# SSD1963-V1_0.net
KiCad netlist of a schematic drawn in EAGLE
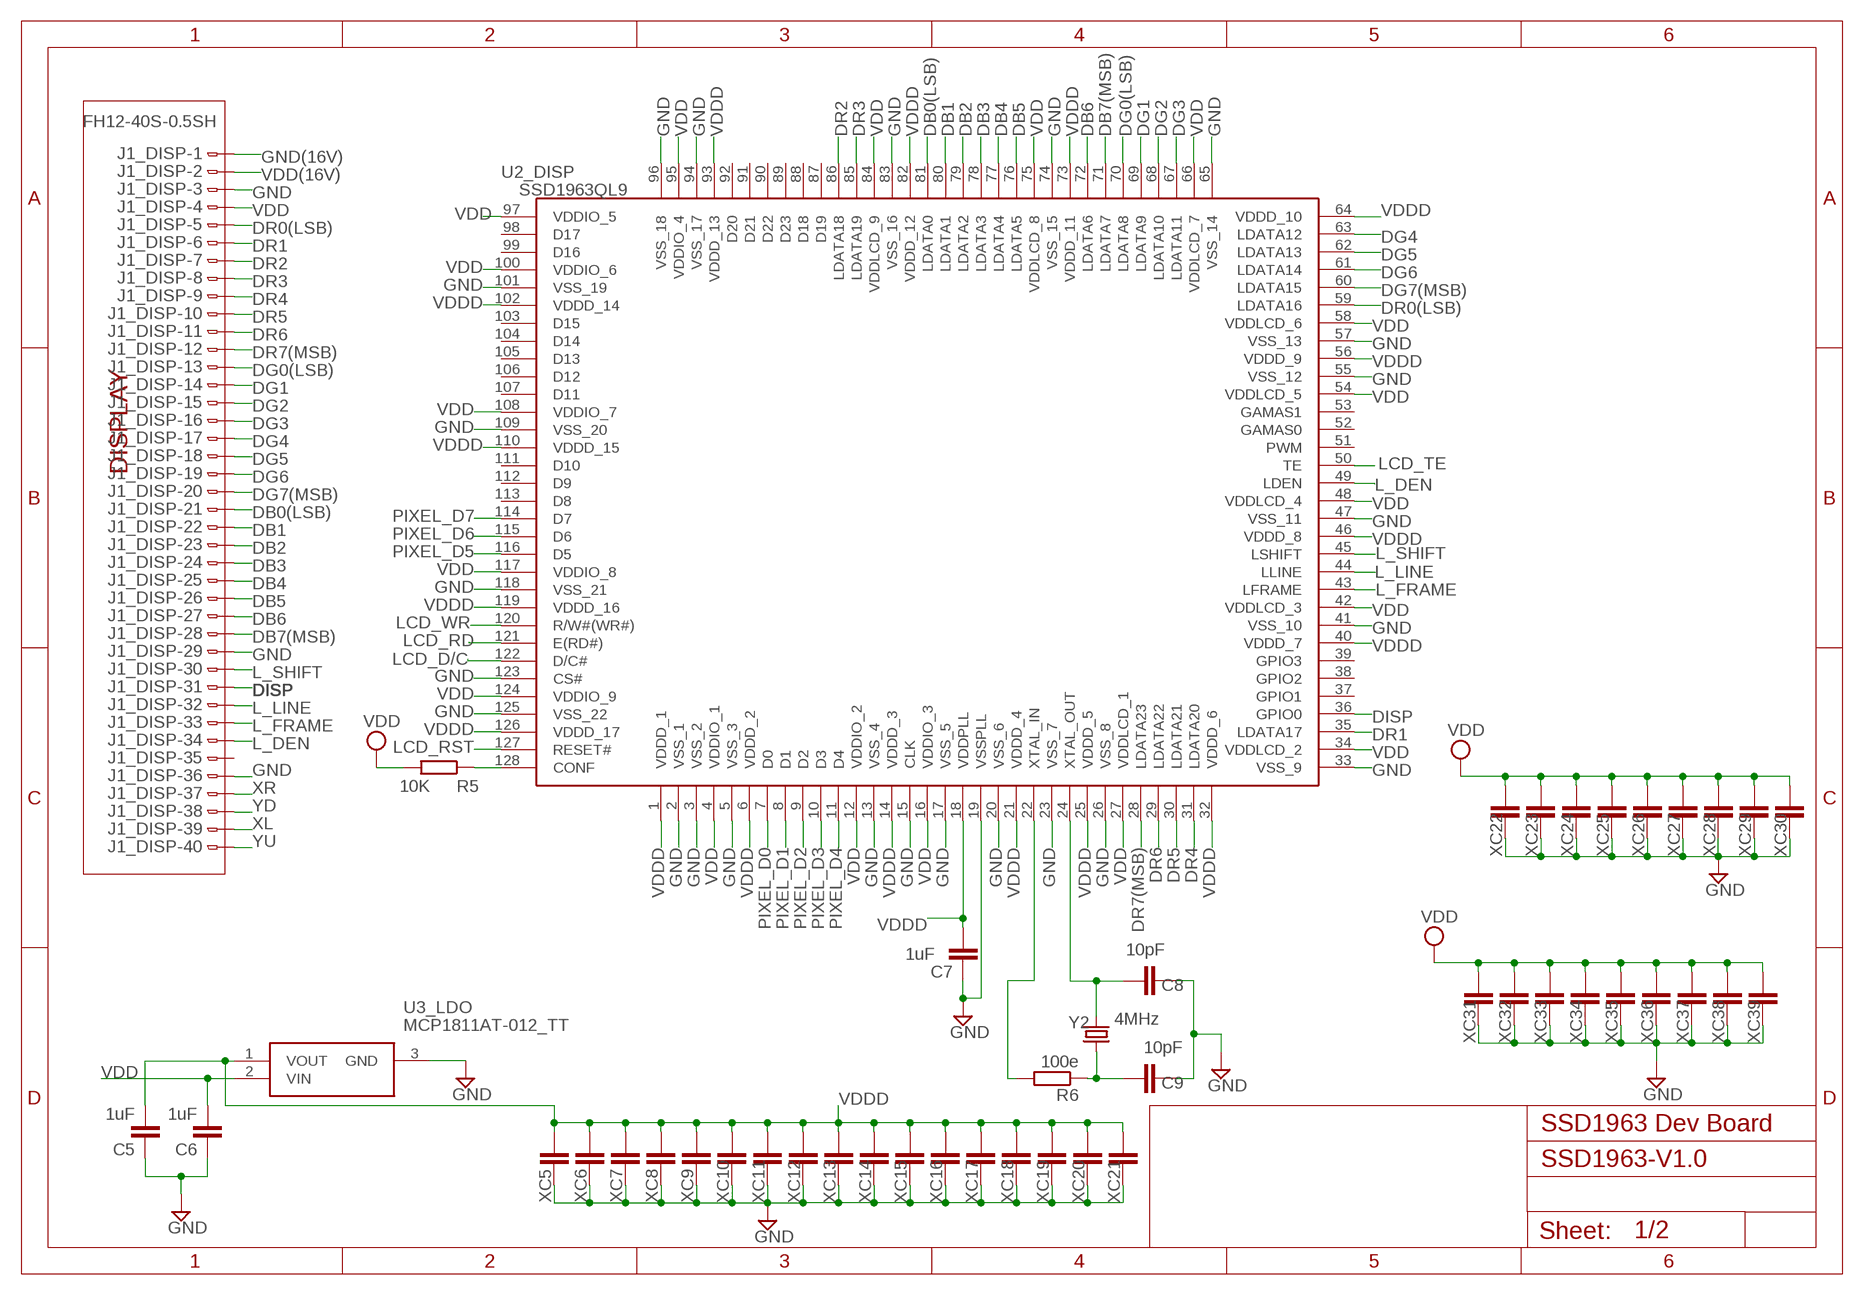
[diagram p0: schematic, sheet 1]
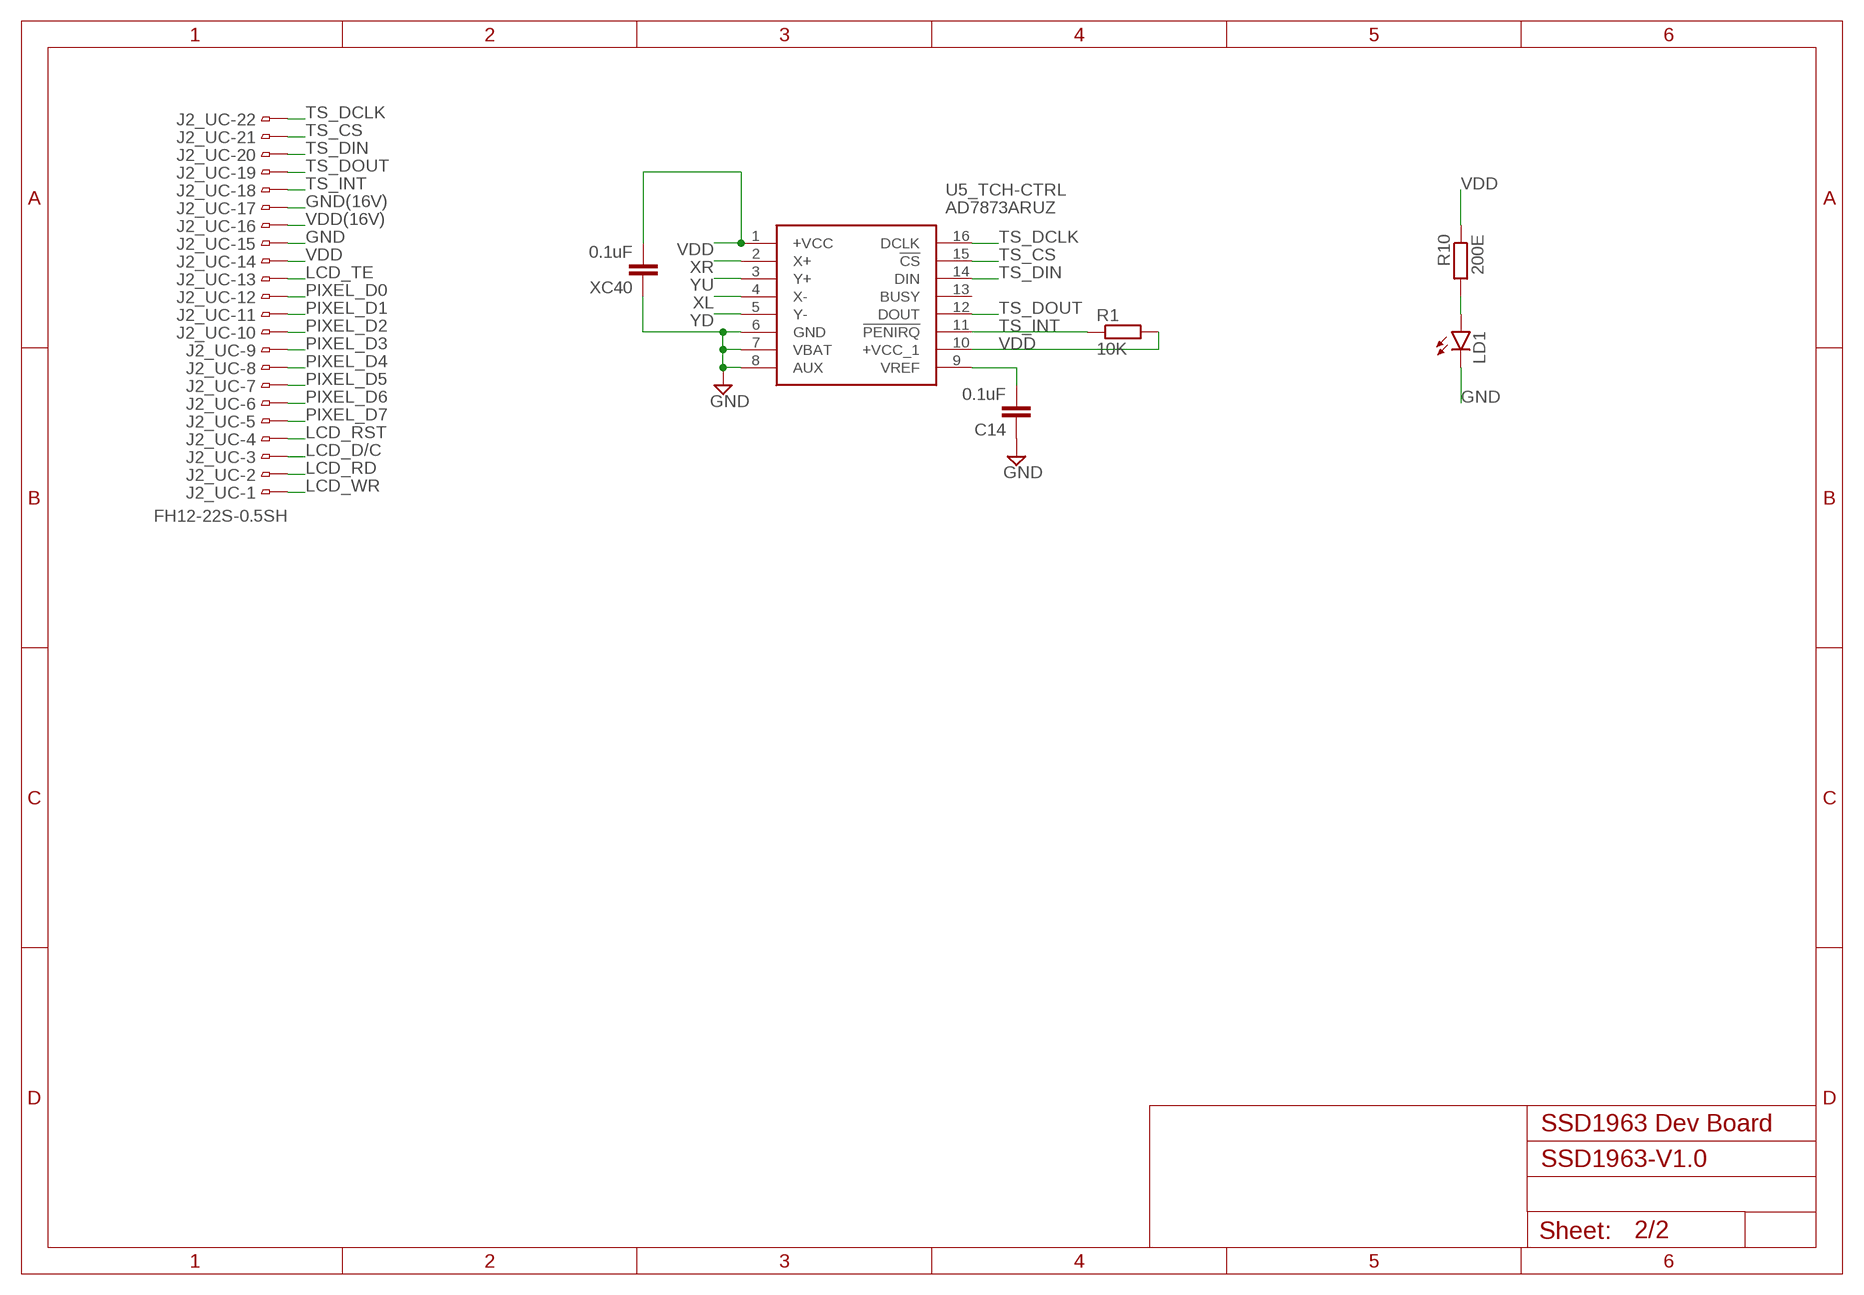
[diagram p1: schematic, sheet 2]

(export (version "E")
  (design (tool "Eeschema 10.0.6"))
  (components
    (comp (ref "C5")
      (value "1uF")
      (footprint "eagle-import:C1206")
      (description "Capacitor")
      (libsource (lib "eagle-import") (part "C-EUC1206"))
    )
    (comp (ref "C6")
      (value "1uF")
      (footprint "eagle-import:C1206")
      (description "Capacitor")
      (libsource (lib "eagle-import") (part "C-EUC1206"))
    )
    (comp (ref "C7")
      (value "1uF")
      (footprint "eagle-import:C0805")
      (description "Capacitor")
      (libsource (lib "eagle-import") (part "C-EUC0805"))
    )
    (comp (ref "C8")
      (value "10pF")
      (footprint "eagle-import:C1206")
      (description "Capacitor")
      (libsource (lib "eagle-import") (part "C-EUC1206"))
    )
    (comp (ref "C9")
      (value "10pF")
      (footprint "eagle-import:C1206")
      (description "Capacitor")
      (libsource (lib "eagle-import") (part "C-EUC1206"))
    )
    (comp (ref "J1_DISP")
      (value "FH12-40S-0.5SH")
      (footprint "eagle-import:FH12-40S-0.5SH")
      (description "0.5mm Pitch Connectors For FPC/FFC")
      (fields (field (name "MPN") "FH12-40S-0.5SH(55)"))
      (libsource (lib "eagle-import") (part "FH12-40S-0.5SH"))
    )
    (comp (ref "R5")
      (value "10K")
      (footprint "eagle-import:R1206")
      (description "Resistor")
      (libsource (lib "eagle-import") (part "R-EU_R1206"))
    )
    (comp (ref "R6")
      (value "100e")
      (footprint "eagle-import:R0805")
      (description "Resistor")
      (libsource (lib "eagle-import") (part "R-EU_R0805"))
    )
    (comp (ref "U2_DISP")
      (value "SSD1963QL9")
      (footprint "eagle-import:QFP40P1600X1600X160-128N")
      (libsource (lib "eagle-import") (part "SSD1963QL9"))
    )
    (comp (ref "U3_LDO")
      (value "MCP1811AT-012_TT")
      (footprint "eagle-import:SOT95P237X112-3N")
      (libsource (lib "eagle-import") (part "MCP1811AT-012_TT"))
    )
    (comp (ref "XC5")
      (value "0.1uF")
      (footprint "eagle-import:C0805")
      (description "Capacitor")
      (libsource (lib "eagle-import") (part "C-EUC0805"))
    )
    (comp (ref "XC6")
      (value "0.1uF")
      (footprint "eagle-import:C0805")
      (description "Capacitor")
      (libsource (lib "eagle-import") (part "C-EUC0805"))
    )
    (comp (ref "XC7")
      (value "0.1uF")
      (footprint "eagle-import:C0805")
      (description "Capacitor")
      (libsource (lib "eagle-import") (part "C-EUC0805"))
    )
    (comp (ref "XC8")
      (value "0.1uF")
      (footprint "eagle-import:C0805")
      (description "Capacitor")
      (libsource (lib "eagle-import") (part "C-EUC0805"))
    )
    (comp (ref "XC9")
      (value "0.1uF")
      (footprint "eagle-import:C0805")
      (description "Capacitor")
      (libsource (lib "eagle-import") (part "C-EUC0805"))
    )
    (comp (ref "XC10")
      (value "0.1uF")
      (footprint "eagle-import:C0805")
      (description "Capacitor")
      (libsource (lib "eagle-import") (part "C-EUC0805"))
    )
    (comp (ref "XC11")
      (value "0.1uF")
      (footprint "eagle-import:C0805")
      (description "Capacitor")
      (libsource (lib "eagle-import") (part "C-EUC0805"))
    )
    (comp (ref "XC12")
      (value "0.1uF")
      (footprint "eagle-import:C0805")
      (description "Capacitor")
      (libsource (lib "eagle-import") (part "C-EUC0805"))
    )
    (comp (ref "XC13")
      (value "0.1uF")
      (footprint "eagle-import:C0805")
      (description "Capacitor")
      (libsource (lib "eagle-import") (part "C-EUC0805"))
    )
    (comp (ref "XC14")
      (value "0.1uF")
      (footprint "eagle-import:C0805")
      (description "Capacitor")
      (libsource (lib "eagle-import") (part "C-EUC0805"))
    )
    (comp (ref "XC15")
      (value "0.1uF")
      (footprint "eagle-import:C0805")
      (description "Capacitor")
      (libsource (lib "eagle-import") (part "C-EUC0805"))
    )
    (comp (ref "XC16")
      (value "0.1uF")
      (footprint "eagle-import:C0805")
      (description "Capacitor")
      (libsource (lib "eagle-import") (part "C-EUC0805"))
    )
    (comp (ref "XC17")
      (value "0.1uF")
      (footprint "eagle-import:C0805")
      (description "Capacitor")
      (libsource (lib "eagle-import") (part "C-EUC0805"))
    )
    (comp (ref "XC18")
      (value "0.1uF")
      (footprint "eagle-import:C0805")
      (description "Capacitor")
      (libsource (lib "eagle-import") (part "C-EUC0805"))
    )
    (comp (ref "XC19")
      (value "0.1uF")
      (footprint "eagle-import:C0805")
      (description "Capacitor")
      (libsource (lib "eagle-import") (part "C-EUC0805"))
    )
    (comp (ref "XC20")
      (value "0.1uF")
      (footprint "eagle-import:C0805")
      (description "Capacitor")
      (libsource (lib "eagle-import") (part "C-EUC0805"))
    )
    (comp (ref "XC21")
      (value "0.1uF")
      (footprint "eagle-import:C0805")
      (description "Capacitor")
      (libsource (lib "eagle-import") (part "C-EUC0805"))
    )
    (comp (ref "XC22")
      (value "0.1uF")
      (footprint "eagle-import:C0805")
      (description "Capacitor")
      (libsource (lib "eagle-import") (part "C-EUC0805"))
    )
    (comp (ref "XC23")
      (value "0.1uF")
      (footprint "eagle-import:C0805")
      (description "Capacitor")
      (libsource (lib "eagle-import") (part "C-EUC0805"))
    )
    (comp (ref "XC24")
      (value "0.1uF")
      (footprint "eagle-import:C0805")
      (description "Capacitor")
      (libsource (lib "eagle-import") (part "C-EUC0805"))
    )
    (comp (ref "XC25")
      (value "0.1uF")
      (footprint "eagle-import:C0805")
      (description "Capacitor")
      (libsource (lib "eagle-import") (part "C-EUC0805"))
    )
    (comp (ref "XC26")
      (value "0.1uF")
      (footprint "eagle-import:C0805")
      (description "Capacitor")
      (libsource (lib "eagle-import") (part "C-EUC0805"))
    )
    (comp (ref "XC27")
      (value "0.1uF")
      (footprint "eagle-import:C0805")
      (description "Capacitor")
      (libsource (lib "eagle-import") (part "C-EUC0805"))
    )
    (comp (ref "XC28")
      (value "0.1uF")
      (footprint "eagle-import:C0805")
      (description "Capacitor")
      (libsource (lib "eagle-import") (part "C-EUC0805"))
    )
    (comp (ref "XC29")
      (value "0.1uF")
      (footprint "eagle-import:C0805")
      (description "Capacitor")
      (libsource (lib "eagle-import") (part "C-EUC0805"))
    )
    (comp (ref "XC30")
      (value "0.1uF")
      (footprint "eagle-import:C0805")
      (description "Capacitor")
      (libsource (lib "eagle-import") (part "C-EUC0805"))
    )
    (comp (ref "XC31")
      (value "0.1uF")
      (footprint "eagle-import:C0805")
      (description "Capacitor")
      (libsource (lib "eagle-import") (part "C-EUC0805"))
    )
    (comp (ref "XC32")
      (value "0.1uF")
      (footprint "eagle-import:C0805")
      (description "Capacitor")
      (libsource (lib "eagle-import") (part "C-EUC0805"))
    )
    (comp (ref "XC33")
      (value "0.1uF")
      (footprint "eagle-import:C0805")
      (description "Capacitor")
      (libsource (lib "eagle-import") (part "C-EUC0805"))
    )
    (comp (ref "XC34")
      (value "0.1uF")
      (footprint "eagle-import:C0805")
      (description "Capacitor")
      (libsource (lib "eagle-import") (part "C-EUC0805"))
    )
    (comp (ref "XC35")
      (value "0.1uF")
      (footprint "eagle-import:C0805")
      (description "Capacitor")
      (libsource (lib "eagle-import") (part "C-EUC0805"))
    )
    (comp (ref "XC36")
      (value "0.1uF")
      (footprint "eagle-import:C0805")
      (description "Capacitor")
      (libsource (lib "eagle-import") (part "C-EUC0805"))
    )
    (comp (ref "XC37")
      (value "0.1uF")
      (footprint "eagle-import:C0805")
      (description "Capacitor")
      (libsource (lib "eagle-import") (part "C-EUC0805"))
    )
    (comp (ref "XC38")
      (value "0.1uF")
      (footprint "eagle-import:C0805")
      (description "Capacitor")
      (libsource (lib "eagle-import") (part "C-EUC0805"))
    )
    (comp (ref "XC39")
      (value "0.1uF")
      (footprint "eagle-import:C0805")
      (description "Capacitor")
      (libsource (lib "eagle-import") (part "C-EUC0805"))
    )
    (comp (ref "Y2")
      (value "4MHz")
      (footprint "eagle-import:HC49UP")
      (description "Crystal 4MHz")
      (libsource (lib "eagle-import") (part "CRYSTALHC49UP"))
    )
    (comp (ref "C14")
      (value "0.1uF")
      (footprint "eagle-import:C1206")
      (description "Capacitor")
      (libsource (lib "eagle-import") (part "C-EUC1206"))
    )
    (comp (ref "J2_UC")
      (value "FH12-22S-0.5SH")
      (footprint "eagle-import:FH12-22S-0.5SH")
      (libsource (lib "eagle-import") (part "FH12-22S-0.5SH"))
    )
    (comp (ref "LD1")
      (value "LEDCHIPLED_1206")
      (footprint "eagle-import:CHIPLED_1206")
      (description "SMD Green LED")
      (libsource (lib "eagle-import") (part "LEDCHIPLED_1206"))
    )
    (comp (ref "R1")
      (value "10K")
      (footprint "eagle-import:R1206")
      (libsource (lib "eagle-import") (part "R-EU_R1206"))
    )
    (comp (ref "R10")
      (value "200E")
      (footprint "eagle-import:R1206")
      (description "Resistor")
      (libsource (lib "eagle-import") (part "R-EU_R1206"))
    )
    (comp (ref "U5_TCH-CTRL")
      (value "AD7873ARUZ")
      (footprint "eagle-import:SOP64P600X175-16N")
      (libsource (lib "eagle-import") (part "AD7873ARUZ"))
    )
    (comp (ref "XC40")
      (value "0.1uF")
      (footprint "eagle-import:C0805")
      (description "Capacitor")
      (libsource (lib "eagle-import") (part "C-EUC0805"))
    )
  )
  (nets
    (net (code "1") (name "DB0(LSB)") (class "Default")
      (node (ref "J1_DISP") (pin "20") (pinfunction "1_20") (pintype "passive"))
      (node (ref "U2_DISP") (pin "81") (pinfunction "LDATA0_81") (pintype "bidirectional"))
    )
    (net (code "2") (name "DB1") (class "Default")
      (node (ref "J1_DISP") (pin "19") (pinfunction "1_19") (pintype "passive"))
      (node (ref "U2_DISP") (pin "80") (pinfunction "LDATA1_80") (pintype "bidirectional"))
    )
    (net (code "3") (name "DB2") (class "Default")
      (node (ref "J1_DISP") (pin "18") (pinfunction "1_18") (pintype "passive"))
      (node (ref "U2_DISP") (pin "79") (pinfunction "LDATA2_79") (pintype "bidirectional"))
    )
    (net (code "4") (name "DB3") (class "Default")
      (node (ref "J1_DISP") (pin "17") (pinfunction "1_17") (pintype "passive"))
      (node (ref "U2_DISP") (pin "78") (pinfunction "LDATA3_78") (pintype "bidirectional"))
    )
    (net (code "5") (name "DB4") (class "Default")
      (node (ref "J1_DISP") (pin "16") (pinfunction "1_16") (pintype "passive"))
      (node (ref "U2_DISP") (pin "77") (pinfunction "LDATA4_77") (pintype "bidirectional"))
    )
    (net (code "6") (name "DB5") (class "Default")
      (node (ref "J1_DISP") (pin "15") (pinfunction "1_15") (pintype "passive"))
      (node (ref "U2_DISP") (pin "76") (pinfunction "LDATA5_76") (pintype "bidirectional"))
    )
    (net (code "7") (name "DB6") (class "Default")
      (node (ref "J1_DISP") (pin "14") (pinfunction "1_14") (pintype "passive"))
      (node (ref "U2_DISP") (pin "72") (pinfunction "LDATA6_72") (pintype "bidirectional"))
    )
    (net (code "8") (name "DB7(MSB)") (class "Default")
      (node (ref "J1_DISP") (pin "13") (pinfunction "1_13") (pintype "passive"))
      (node (ref "U2_DISP") (pin "71") (pinfunction "LDATA7_71") (pintype "bidirectional"))
    )
    (net (code "9") (name "DG0(LSB)") (class "Default")
      (node (ref "J1_DISP") (pin "28") (pinfunction "1_28") (pintype "passive"))
      (node (ref "U2_DISP") (pin "70") (pinfunction "LDATA8_70") (pintype "bidirectional"))
    )
    (net (code "10") (name "DG1") (class "Default")
      (node (ref "J1_DISP") (pin "27") (pinfunction "1_27") (pintype "passive"))
      (node (ref "U2_DISP") (pin "69") (pinfunction "LDATA9_69") (pintype "bidirectional"))
    )
    (net (code "11") (name "DG2") (class "Default")
      (node (ref "J1_DISP") (pin "26") (pinfunction "1_26") (pintype "passive"))
      (node (ref "U2_DISP") (pin "68") (pinfunction "LDATA10_68") (pintype "bidirectional"))
    )
    (net (code "12") (name "DG3") (class "Default")
      (node (ref "J1_DISP") (pin "25") (pinfunction "1_25") (pintype "passive"))
      (node (ref "U2_DISP") (pin "67") (pinfunction "LDATA11_67") (pintype "bidirectional"))
    )
    (net (code "13") (name "DG4") (class "Default")
      (node (ref "J1_DISP") (pin "24") (pinfunction "1_24") (pintype "passive"))
      (node (ref "U2_DISP") (pin "63") (pinfunction "LDATA12_63") (pintype "bidirectional"))
    )
    (net (code "14") (name "DG5") (class "Default")
      (node (ref "J1_DISP") (pin "23") (pinfunction "1_23") (pintype "passive"))
      (node (ref "U2_DISP") (pin "62") (pinfunction "LDATA13_62") (pintype "bidirectional"))
    )
    (net (code "15") (name "DG6") (class "Default")
      (node (ref "J1_DISP") (pin "22") (pinfunction "1_22") (pintype "passive"))
      (node (ref "U2_DISP") (pin "61") (pinfunction "LDATA14_61") (pintype "bidirectional"))
    )
    (net (code "16") (name "DG7(MSB)") (class "Default")
      (node (ref "J1_DISP") (pin "21") (pinfunction "1_21") (pintype "passive"))
      (node (ref "U2_DISP") (pin "60") (pinfunction "LDATA15_60") (pintype "bidirectional"))
    )
    (net (code "17") (name "DISP") (class "Default")
      (node (ref "J1_DISP") (pin "10") (pinfunction "1_10") (pintype "passive"))
      (node (ref "U2_DISP") (pin "36") (pinfunction "GPIO0_36") (pintype "bidirectional"))
    )
    (net (code "18") (name "DR0(LSB)") (class "Default")
      (node (ref "J1_DISP") (pin "36") (pinfunction "1_36") (pintype "passive"))
      (node (ref "U2_DISP") (pin "59") (pinfunction "LDATA16_59") (pintype "bidirectional"))
    )
    (net (code "19") (name "DR1") (class "Default")
      (node (ref "J1_DISP") (pin "35") (pinfunction "1_35") (pintype "passive"))
      (node (ref "U2_DISP") (pin "35") (pinfunction "LDATA17_35") (pintype "bidirectional"))
    )
    (net (code "20") (name "DR2") (class "Default")
      (node (ref "J1_DISP") (pin "34") (pinfunction "1_34") (pintype "passive"))
      (node (ref "U2_DISP") (pin "86") (pinfunction "LDATA18_86") (pintype "bidirectional"))
    )
    (net (code "21") (name "DR3") (class "Default")
      (node (ref "J1_DISP") (pin "33") (pinfunction "1_33") (pintype "passive"))
      (node (ref "U2_DISP") (pin "85") (pinfunction "LDATA19_85") (pintype "bidirectional"))
    )
    (net (code "22") (name "DR4") (class "Default")
      (node (ref "J1_DISP") (pin "32") (pinfunction "1_32") (pintype "passive"))
      (node (ref "U2_DISP") (pin "31") (pinfunction "LDATA20_31") (pintype "bidirectional"))
    )
    (net (code "23") (name "DR5") (class "Default")
      (node (ref "J1_DISP") (pin "31") (pinfunction "1_31") (pintype "passive"))
      (node (ref "U2_DISP") (pin "30") (pinfunction "LDATA21_30") (pintype "bidirectional"))
    )
    (net (code "24") (name "DR6") (class "Default")
      (node (ref "J1_DISP") (pin "30") (pinfunction "1_30") (pintype "passive"))
      (node (ref "U2_DISP") (pin "29") (pinfunction "LDATA22_29") (pintype "bidirectional"))
    )
    (net (code "25") (name "DR7(MSB)") (class "Default")
      (node (ref "J1_DISP") (pin "29") (pinfunction "1_29") (pintype "passive"))
      (node (ref "U2_DISP") (pin "28") (pinfunction "LDATA23_28") (pintype "bidirectional"))
    )
    (net (code "26") (name "GND") (class "Default")
      (node (ref "C14") (pin "1") (pinfunction "1_1") (pintype "passive"))
      (node (ref "C5") (pin "1") (pinfunction "1_1") (pintype "passive"))
      (node (ref "C6") (pin "1") (pinfunction "1_1") (pintype "passive"))
      (node (ref "C7") (pin "1") (pinfunction "1_1") (pintype "passive"))
      (node (ref "C8") (pin "1") (pinfunction "1_1") (pintype "passive"))
      (node (ref "C9") (pin "1") (pinfunction "1_1") (pintype "passive"))
      (node (ref "J1_DISP") (pin "12") (pinfunction "1_12") (pintype "passive"))
      (node (ref "J1_DISP") (pin "38") (pinfunction "1_38") (pintype "passive"))
      (node (ref "J1_DISP") (pin "5") (pinfunction "1_5") (pintype "passive"))
      (node (ref "J2_UC") (pin "15") (pinfunction "1_15") (pintype "passive"))
      (node (ref "LD1") (pin "C") (pinfunction "C_C") (pintype "passive"))
      (node (ref "U2_DISP") (pin "101") (pinfunction "VSS_19_101") (pintype "bidirectional"))
      (node (ref "U2_DISP") (pin "109") (pinfunction "VSS_20_109") (pintype "bidirectional"))
      (node (ref "U2_DISP") (pin "118") (pinfunction "VSS_21_118") (pintype "bidirectional"))
      (node (ref "U2_DISP") (pin "123") (pinfunction "CS#_123") (pintype "bidirectional"))
      (node (ref "U2_DISP") (pin "125") (pinfunction "VSS_22_125") (pintype "bidirectional"))
      (node (ref "U2_DISP") (pin "13") (pinfunction "VSS_4_13") (pintype "bidirectional"))
      (node (ref "U2_DISP") (pin "15") (pinfunction "CLK_15") (pintype "bidirectional"))
      (node (ref "U2_DISP") (pin "17") (pinfunction "VSS_5_17") (pintype "bidirectional"))
      (node (ref "U2_DISP") (pin "19") (pinfunction "VSSPLL_19") (pintype "bidirectional"))
      (node (ref "U2_DISP") (pin "2") (pinfunction "VSS_1_2") (pintype "bidirectional"))
      (node (ref "U2_DISP") (pin "20") (pinfunction "VSS_6_20") (pintype "bidirectional"))
      (node (ref "U2_DISP") (pin "23") (pinfunction "VSS_7_23") (pintype "bidirectional"))
      (node (ref "U2_DISP") (pin "26") (pinfunction "VSS_8_26") (pintype "bidirectional"))
      (node (ref "U2_DISP") (pin "3") (pinfunction "VSS_2_3") (pintype "bidirectional"))
      (node (ref "U2_DISP") (pin "33") (pinfunction "VSS_9_33") (pintype "bidirectional"))
      (node (ref "U2_DISP") (pin "41") (pinfunction "VSS_10_41") (pintype "bidirectional"))
      (node (ref "U2_DISP") (pin "47") (pinfunction "VSS_11_47") (pintype "bidirectional"))
      (node (ref "U2_DISP") (pin "5") (pinfunction "VSS_3_5") (pintype "bidirectional"))
      (node (ref "U2_DISP") (pin "55") (pinfunction "VSS_12_55") (pintype "bidirectional"))
      (node (ref "U2_DISP") (pin "57") (pinfunction "VSS_13_57") (pintype "bidirectional"))
      (node (ref "U2_DISP") (pin "65") (pinfunction "VSS_14_65") (pintype "bidirectional"))
      (node (ref "U2_DISP") (pin "74") (pinfunction "VSS_15_74") (pintype "bidirectional"))
      (node (ref "U2_DISP") (pin "83") (pinfunction "VSS_16_83") (pintype "bidirectional"))
      (node (ref "U2_DISP") (pin "94") (pinfunction "VSS_17_94") (pintype "bidirectional"))
      (node (ref "U2_DISP") (pin "96") (pinfunction "VSS_18_96") (pintype "bidirectional"))
      (node (ref "U3_LDO") (pin "3") (pinfunction "GND_3") (pintype "bidirectional"))
      (node (ref "U5_TCH-CTRL") (pin "6") (pinfunction "GND_6") (pintype "power_in"))
      (node (ref "U5_TCH-CTRL") (pin "7") (pinfunction "VBAT_7") (pintype "bidirectional"))
      (node (ref "U5_TCH-CTRL") (pin "8") (pinfunction "AUX_8") (pintype "bidirectional"))
      (node (ref "XC10") (pin "1") (pinfunction "1_1") (pintype "passive"))
      (node (ref "XC11") (pin "1") (pinfunction "1_1") (pintype "passive"))
      (node (ref "XC12") (pin "1") (pinfunction "1_1") (pintype "passive"))
      (node (ref "XC13") (pin "1") (pinfunction "1_1") (pintype "passive"))
      (node (ref "XC14") (pin "1") (pinfunction "1_1") (pintype "passive"))
      (node (ref "XC15") (pin "1") (pinfunction "1_1") (pintype "passive"))
      (node (ref "XC16") (pin "1") (pinfunction "1_1") (pintype "passive"))
      (node (ref "XC17") (pin "1") (pinfunction "1_1") (pintype "passive"))
      (node (ref "XC18") (pin "1") (pinfunction "1_1") (pintype "passive"))
      (node (ref "XC19") (pin "1") (pinfunction "1_1") (pintype "passive"))
      (node (ref "XC20") (pin "1") (pinfunction "1_1") (pintype "passive"))
      (node (ref "XC21") (pin "1") (pinfunction "1_1") (pintype "passive"))
      (node (ref "XC22") (pin "1") (pinfunction "1_1") (pintype "passive"))
      (node (ref "XC23") (pin "1") (pinfunction "1_1") (pintype "passive"))
      (node (ref "XC24") (pin "1") (pinfunction "1_1") (pintype "passive"))
      (node (ref "XC25") (pin "1") (pinfunction "1_1") (pintype "passive"))
      (node (ref "XC26") (pin "1") (pinfunction "1_1") (pintype "passive"))
      (node (ref "XC27") (pin "1") (pinfunction "1_1") (pintype "passive"))
      (node (ref "XC28") (pin "1") (pinfunction "1_1") (pintype "passive"))
      (node (ref "XC29") (pin "1") (pinfunction "1_1") (pintype "passive"))
      (node (ref "XC30") (pin "1") (pinfunction "1_1") (pintype "passive"))
      (node (ref "XC31") (pin "1") (pinfunction "1_1") (pintype "passive"))
      (node (ref "XC32") (pin "1") (pinfunction "1_1") (pintype "passive"))
      (node (ref "XC33") (pin "1") (pinfunction "1_1") (pintype "passive"))
      (node (ref "XC34") (pin "1") (pinfunction "1_1") (pintype "passive"))
      (node (ref "XC35") (pin "1") (pinfunction "1_1") (pintype "passive"))
      (node (ref "XC36") (pin "1") (pinfunction "1_1") (pintype "passive"))
      (node (ref "XC37") (pin "1") (pinfunction "1_1") (pintype "passive"))
      (node (ref "XC38") (pin "1") (pinfunction "1_1") (pintype "passive"))
      (node (ref "XC39") (pin "1") (pinfunction "1_1") (pintype "passive"))
      (node (ref "XC40") (pin "1") (pinfunction "1_1") (pintype "passive"))
      (node (ref "XC5") (pin "1") (pinfunction "1_1") (pintype "passive"))
      (node (ref "XC6") (pin "1") (pinfunction "1_1") (pintype "passive"))
      (node (ref "XC7") (pin "1") (pinfunction "1_1") (pintype "passive"))
      (node (ref "XC8") (pin "1") (pinfunction "1_1") (pintype "passive"))
      (node (ref "XC9") (pin "1") (pinfunction "1_1") (pintype "passive"))
    )
    (net (code "27") (name "GND(16V)") (class "Default")
      (node (ref "J1_DISP") (pin "40") (pinfunction "1_40") (pintype "passive"))
      (node (ref "J2_UC") (pin "17") (pinfunction "1_17") (pintype "passive"))
    )
    (net (code "28") (name "LCD_D{slash}C") (class "Default")
      (node (ref "J2_UC") (pin "3") (pinfunction "1_3") (pintype "passive"))
      (node (ref "U2_DISP") (pin "122") (pinfunction "D/C#_122") (pintype "bidirectional"))
    )
    (net (code "29") (name "LCD_RD") (class "Default")
      (node (ref "J2_UC") (pin "2") (pinfunction "1_2") (pintype "passive"))
      (node (ref "U2_DISP") (pin "121") (pinfunction "E(RD#)_121") (pintype "bidirectional"))
    )
    (net (code "30") (name "LCD_RST") (class "Default")
      (node (ref "J2_UC") (pin "4") (pinfunction "1_4") (pintype "passive"))
      (node (ref "U2_DISP") (pin "127") (pinfunction "RESET#_127") (pintype "bidirectional"))
    )
    (net (code "31") (name "LCD_TE") (class "Default")
      (node (ref "J2_UC") (pin "13") (pinfunction "1_13") (pintype "passive"))
      (node (ref "U2_DISP") (pin "50") (pinfunction "TE_50") (pintype "bidirectional"))
    )
    (net (code "32") (name "LCD_WR") (class "Default")
      (node (ref "J2_UC") (pin "1") (pinfunction "1_1") (pintype "passive"))
      (node (ref "U2_DISP") (pin "120") (pinfunction "R/W#(WR#)_120") (pintype "bidirectional"))
    )
    (net (code "33") (name "L_DEN") (class "Default")
      (node (ref "J1_DISP") (pin "7") (pinfunction "1_7") (pintype "passive"))
      (node (ref "U2_DISP") (pin "49") (pinfunction "LDEN_49") (pintype "bidirectional"))
    )
    (net (code "34") (name "L_FRAME") (class "Default")
      (node (ref "J1_DISP") (pin "8") (pinfunction "1_8") (pintype "passive"))
      (node (ref "U2_DISP") (pin "43") (pinfunction "LFRAME_43") (pintype "bidirectional"))
    )
    (net (code "35") (name "L_LINE") (class "Default")
      (node (ref "J1_DISP") (pin "9") (pinfunction "1_9") (pintype "passive"))
      (node (ref "U2_DISP") (pin "44") (pinfunction "LLINE_44") (pintype "bidirectional"))
    )
    (net (code "36") (name "L_SHIFT") (class "Default")
      (node (ref "J1_DISP") (pin "11") (pinfunction "1_11") (pintype "passive"))
      (node (ref "U2_DISP") (pin "45") (pinfunction "LSHIFT_45") (pintype "bidirectional"))
    )
    (net (code "37") (name "Net-(C9-Pad2)") (class "Default")
      (node (ref "C9") (pin "2") (pinfunction "2_2") (pintype "passive"))
      (node (ref "R6") (pin "1") (pinfunction "1_1") (pintype "passive"))
      (node (ref "Y2") (pin "1") (pinfunction "1_1") (pintype "passive"))
    )
    (net (code "38") (name "Net-(LD1-PadA)") (class "Default")
      (node (ref "LD1") (pin "A") (pinfunction "A_A") (pintype "passive"))
      (node (ref "R10") (pin "2") (pinfunction "2_2") (pintype "passive"))
    )
    (net (code "39") (name "Net-(U2_DISP-CONF)") (class "Default")
      (node (ref "R5") (pin "1") (pinfunction "1_1") (pintype "passive"))
      (node (ref "U2_DISP") (pin "128") (pinfunction "CONF_128") (pintype "bidirectional"))
    )
    (net (code "40") (name "Net-(U2_DISP-XTAL_IN)") (class "Default")
      (node (ref "R6") (pin "2") (pinfunction "2_2") (pintype "passive"))
      (node (ref "U2_DISP") (pin "22") (pinfunction "XTAL_IN_22") (pintype "bidirectional"))
    )
    (net (code "41") (name "Net-(U2_DISP-XTAL_OUT)") (class "Default")
      (node (ref "C8") (pin "2") (pinfunction "2_2") (pintype "passive"))
      (node (ref "U2_DISP") (pin "24") (pinfunction "XTAL_OUT_24") (pintype "bidirectional"))
      (node (ref "Y2") (pin "2") (pinfunction "2_2") (pintype "passive"))
    )
    (net (code "42") (name "Net-(U5_TCH-CTRL-VREF)") (class "Default")
      (node (ref "C14") (pin "2") (pinfunction "2_2") (pintype "passive"))
      (node (ref "U5_TCH-CTRL") (pin "9") (pinfunction "VREF_9") (pintype "input"))
    )
    (net (code "43") (name "PIXEL_D0") (class "Default")
      (node (ref "J2_UC") (pin "12") (pinfunction "1_12") (pintype "passive"))
      (node (ref "U2_DISP") (pin "7") (pinfunction "D0_7") (pintype "bidirectional"))
    )
    (net (code "44") (name "PIXEL_D1") (class "Default")
      (node (ref "J2_UC") (pin "11") (pinfunction "1_11") (pintype "passive"))
      (node (ref "U2_DISP") (pin "8") (pinfunction "D1_8") (pintype "bidirectional"))
    )
    (net (code "45") (name "PIXEL_D2") (class "Default")
      (node (ref "J2_UC") (pin "10") (pinfunction "1_10") (pintype "passive"))
      (node (ref "U2_DISP") (pin "9") (pinfunction "D2_9") (pintype "bidirectional"))
    )
    (net (code "46") (name "PIXEL_D3") (class "Default")
      (node (ref "J2_UC") (pin "9") (pinfunction "1_9") (pintype "passive"))
      (node (ref "U2_DISP") (pin "10") (pinfunction "D3_10") (pintype "bidirectional"))
    )
    (net (code "47") (name "PIXEL_D4") (class "Default")
      (node (ref "J2_UC") (pin "8") (pinfunction "1_8") (pintype "passive"))
      (node (ref "U2_DISP") (pin "11") (pinfunction "D4_11") (pintype "bidirectional"))
    )
    (net (code "48") (name "PIXEL_D5") (class "Default")
      (node (ref "J2_UC") (pin "7") (pinfunction "1_7") (pintype "passive"))
      (node (ref "U2_DISP") (pin "116") (pinfunction "D5_116") (pintype "bidirectional"))
    )
    (net (code "49") (name "PIXEL_D6") (class "Default")
      (node (ref "J2_UC") (pin "6") (pinfunction "1_6") (pintype "passive"))
      (node (ref "U2_DISP") (pin "115") (pinfunction "D6_115") (pintype "bidirectional"))
    )
    (net (code "50") (name "PIXEL_D7") (class "Default")
      (node (ref "J2_UC") (pin "5") (pinfunction "1_5") (pintype "passive"))
      (node (ref "U2_DISP") (pin "114") (pinfunction "D7_114") (pintype "bidirectional"))
    )
    (net (code "51") (name "TS_CS") (class "Default")
      (node (ref "J2_UC") (pin "21") (pinfunction "1_21") (pintype "passive"))
      (node (ref "U5_TCH-CTRL") (pin "15") (pinfunction "~{CS}_15") (pintype "input"))
    )
    (net (code "52") (name "TS_DCLK") (class "Default")
      (node (ref "J2_UC") (pin "22") (pinfunction "1_22") (pintype "passive"))
      (node (ref "U5_TCH-CTRL") (pin "16") (pinfunction "DCLK_16") (pintype "input"))
    )
    (net (code "53") (name "TS_DIN") (class "Default")
      (node (ref "J2_UC") (pin "20") (pinfunction "1_20") (pintype "passive"))
      (node (ref "U5_TCH-CTRL") (pin "14") (pinfunction "DIN_14") (pintype "input"))
    )
    (net (code "54") (name "TS_DOUT") (class "Default")
      (node (ref "J2_UC") (pin "19") (pinfunction "1_19") (pintype "passive"))
      (node (ref "U5_TCH-CTRL") (pin "12") (pinfunction "DOUT_12") (pintype "output"))
    )
    (net (code "55") (name "TS_INT") (class "Default")
      (node (ref "J2_UC") (pin "18") (pinfunction "1_18") (pintype "passive"))
      (node (ref "R1") (pin "1") (pinfunction "1_1") (pintype "passive"))
      (node (ref "U5_TCH-CTRL") (pin "11") (pinfunction "~{PENIRQ}_11") (pintype "bidirectional"))
    )
    (net (code "56") (name "VDD") (class "Default")
      (node (ref "C6") (pin "2") (pinfunction "2_2") (pintype "passive"))
      (node (ref "J1_DISP") (pin "37") (pinfunction "1_37") (pintype "passive"))
      (node (ref "J2_UC") (pin "14") (pinfunction "1_14") (pintype "passive"))
      (node (ref "R1") (pin "2") (pinfunction "2_2") (pintype "passive"))
      (node (ref "R10") (pin "1") (pinfunction "1_1") (pintype "passive"))
      (node (ref "R5") (pin "2") (pinfunction "2_2") (pintype "passive"))
      (node (ref "U2_DISP") (pin "100") (pinfunction "VDDIO_6_100") (pintype "bidirectional"))
      (node (ref "U2_DISP") (pin "108") (pinfunction "VDDIO_7_108") (pintype "bidirectional"))
      (node (ref "U2_DISP") (pin "117") (pinfunction "VDDIO_8_117") (pintype "bidirectional"))
      (node (ref "U2_DISP") (pin "12") (pinfunction "VDDIO_2_12") (pintype "bidirectional"))
      (node (ref "U2_DISP") (pin "124") (pinfunction "VDDIO_9_124") (pintype "bidirectional"))
      (node (ref "U2_DISP") (pin "16") (pinfunction "VDDIO_3_16") (pintype "bidirectional"))
      (node (ref "U2_DISP") (pin "27") (pinfunction "VDDLCD_1_27") (pintype "bidirectional"))
      (node (ref "U2_DISP") (pin "34") (pinfunction "VDDLCD_2_34") (pintype "bidirectional"))
      (node (ref "U2_DISP") (pin "4") (pinfunction "VDDIO_1_4") (pintype "bidirectional"))
      (node (ref "U2_DISP") (pin "42") (pinfunction "VDDLCD_3_42") (pintype "bidirectional"))
      (node (ref "U2_DISP") (pin "48") (pinfunction "VDDLCD_4_48") (pintype "bidirectional"))
      (node (ref "U2_DISP") (pin "54") (pinfunction "VDDLCD_5_54") (pintype "bidirectional"))
      (node (ref "U2_DISP") (pin "58") (pinfunction "VDDLCD_6_58") (pintype "bidirectional"))
      (node (ref "U2_DISP") (pin "66") (pinfunction "VDDLCD_7_66") (pintype "bidirectional"))
      (node (ref "U2_DISP") (pin "75") (pinfunction "VDDLCD_8_75") (pintype "bidirectional"))
      (node (ref "U2_DISP") (pin "84") (pinfunction "VDDLCD_9_84") (pintype "bidirectional"))
      (node (ref "U2_DISP") (pin "95") (pinfunction "VDDIO_4_95") (pintype "bidirectional"))
      (node (ref "U2_DISP") (pin "97") (pinfunction "VDDIO_5_97") (pintype "bidirectional"))
      (node (ref "U3_LDO") (pin "2") (pinfunction "VIN_2") (pintype "bidirectional"))
      (node (ref "U5_TCH-CTRL") (pin "1") (pinfunction "+VCC_1") (pintype "power_in"))
      (node (ref "U5_TCH-CTRL") (pin "10") (pinfunction "+VCC_1_10") (pintype "power_in"))
      (node (ref "XC22") (pin "2") (pinfunction "2_2") (pintype "passive"))
      (node (ref "XC23") (pin "2") (pinfunction "2_2") (pintype "passive"))
      (node (ref "XC24") (pin "2") (pinfunction "2_2") (pintype "passive"))
      (node (ref "XC25") (pin "2") (pinfunction "2_2") (pintype "passive"))
      (node (ref "XC26") (pin "2") (pinfunction "2_2") (pintype "passive"))
      (node (ref "XC27") (pin "2") (pinfunction "2_2") (pintype "passive"))
      (node (ref "XC28") (pin "2") (pinfunction "2_2") (pintype "passive"))
      (node (ref "XC29") (pin "2") (pinfunction "2_2") (pintype "passive"))
      (node (ref "XC30") (pin "2") (pinfunction "2_2") (pintype "passive"))
      (node (ref "XC31") (pin "2") (pinfunction "2_2") (pintype "passive"))
      (node (ref "XC32") (pin "2") (pinfunction "2_2") (pintype "passive"))
      (node (ref "XC33") (pin "2") (pinfunction "2_2") (pintype "passive"))
      (node (ref "XC34") (pin "2") (pinfunction "2_2") (pintype "passive"))
      (node (ref "XC35") (pin "2") (pinfunction "2_2") (pintype "passive"))
      (node (ref "XC36") (pin "2") (pinfunction "2_2") (pintype "passive"))
      (node (ref "XC37") (pin "2") (pinfunction "2_2") (pintype "passive"))
      (node (ref "XC38") (pin "2") (pinfunction "2_2") (pintype "passive"))
      (node (ref "XC39") (pin "2") (pinfunction "2_2") (pintype "passive"))
      (node (ref "XC40") (pin "2") (pinfunction "2_2") (pintype "passive"))
    )
    (net (code "57") (name "VDD(16V)") (class "Default")
      (node (ref "J1_DISP") (pin "39") (pinfunction "1_39") (pintype "passive"))
      (node (ref "J2_UC") (pin "16") (pinfunction "1_16") (pintype "passive"))
    )
    (net (code "58") (name "VDDD") (class "Default")
      (node (ref "C5") (pin "2") (pinfunction "2_2") (pintype "passive"))
      (node (ref "C7") (pin "2") (pinfunction "2_2") (pintype "passive"))
      (node (ref "U2_DISP") (pin "1") (pinfunction "VDDD_1_1") (pintype "bidirectional"))
      (node (ref "U2_DISP") (pin "102") (pinfunction "VDDD_14_102") (pintype "bidirectional"))
      (node (ref "U2_DISP") (pin "110") (pinfunction "VDDD_15_110") (pintype "bidirectional"))
      (node (ref "U2_DISP") (pin "119") (pinfunction "VDDD_16_119") (pintype "bidirectional"))
      (node (ref "U2_DISP") (pin "126") (pinfunction "VDDD_17_126") (pintype "bidirectional"))
      (node (ref "U2_DISP") (pin "14") (pinfunction "VDDD_3_14") (pintype "bidirectional"))
      (node (ref "U2_DISP") (pin "18") (pinfunction "VDDPLL_18") (pintype "bidirectional"))
      (node (ref "U2_DISP") (pin "21") (pinfunction "VDDD_4_21") (pintype "bidirectional"))
      (node (ref "U2_DISP") (pin "25") (pinfunction "VDDD_5_25") (pintype "bidirectional"))
      (node (ref "U2_DISP") (pin "32") (pinfunction "VDDD_6_32") (pintype "bidirectional"))
      (node (ref "U2_DISP") (pin "40") (pinfunction "VDDD_7_40") (pintype "bidirectional"))
      (node (ref "U2_DISP") (pin "46") (pinfunction "VDDD_8_46") (pintype "bidirectional"))
      (node (ref "U2_DISP") (pin "56") (pinfunction "VDDD_9_56") (pintype "bidirectional"))
      (node (ref "U2_DISP") (pin "6") (pinfunction "VDDD_2_6") (pintype "bidirectional"))
      (node (ref "U2_DISP") (pin "64") (pinfunction "VDDD_10_64") (pintype "bidirectional"))
      (node (ref "U2_DISP") (pin "73") (pinfunction "VDDD_11_73") (pintype "bidirectional"))
      (node (ref "U2_DISP") (pin "82") (pinfunction "VDDD_12_82") (pintype "bidirectional"))
      (node (ref "U2_DISP") (pin "93") (pinfunction "VDDD_13_93") (pintype "bidirectional"))
      (node (ref "U3_LDO") (pin "1") (pinfunction "VOUT_1") (pintype "bidirectional"))
      (node (ref "XC10") (pin "2") (pinfunction "2_2") (pintype "passive"))
      (node (ref "XC11") (pin "2") (pinfunction "2_2") (pintype "passive"))
      (node (ref "XC12") (pin "2") (pinfunction "2_2") (pintype "passive"))
      (node (ref "XC13") (pin "2") (pinfunction "2_2") (pintype "passive"))
      (node (ref "XC14") (pin "2") (pinfunction "2_2") (pintype "passive"))
      (node (ref "XC15") (pin "2") (pinfunction "2_2") (pintype "passive"))
      (node (ref "XC16") (pin "2") (pinfunction "2_2") (pintype "passive"))
      (node (ref "XC17") (pin "2") (pinfunction "2_2") (pintype "passive"))
      (node (ref "XC18") (pin "2") (pinfunction "2_2") (pintype "passive"))
      (node (ref "XC19") (pin "2") (pinfunction "2_2") (pintype "passive"))
      (node (ref "XC20") (pin "2") (pinfunction "2_2") (pintype "passive"))
      (node (ref "XC21") (pin "2") (pinfunction "2_2") (pintype "passive"))
      (node (ref "XC5") (pin "2") (pinfunction "2_2") (pintype "passive"))
      (node (ref "XC6") (pin "2") (pinfunction "2_2") (pintype "passive"))
      (node (ref "XC7") (pin "2") (pinfunction "2_2") (pintype "passive"))
      (node (ref "XC8") (pin "2") (pinfunction "2_2") (pintype "passive"))
      (node (ref "XC9") (pin "2") (pinfunction "2_2") (pintype "passive"))
    )
    (net (code "59") (name "XL") (class "Default")
      (node (ref "J1_DISP") (pin "2") (pinfunction "1_2") (pintype "passive"))
      (node (ref "U5_TCH-CTRL") (pin "4") (pinfunction "X-_4") (pintype "bidirectional"))
    )
    (net (code "60") (name "XR") (class "Default")
      (node (ref "J1_DISP") (pin "4") (pinfunction "1_4") (pintype "passive"))
      (node (ref "U5_TCH-CTRL") (pin "2") (pinfunction "X+_2") (pintype "bidirectional"))
    )
    (net (code "61") (name "YD") (class "Default")
      (node (ref "J1_DISP") (pin "3") (pinfunction "1_3") (pintype "passive"))
      (node (ref "U5_TCH-CTRL") (pin "5") (pinfunction "Y-_5") (pintype "bidirectional"))
    )
    (net (code "62") (name "YU") (class "Default")
      (node (ref "J1_DISP") (pin "1") (pinfunction "1_1") (pintype "passive"))
      (node (ref "U5_TCH-CTRL") (pin "3") (pinfunction "Y+_3") (pintype "bidirectional"))
    )
    (net (code "63") (name "unconnected-(J1_DISPAC-1-Pad6)") (class "Default")
      (node (ref "J1_DISP") (pin "6") (pinfunction "1_6") (pintype "passive"))
    )
    (net (code "64") (name "unconnected-(U2_DISP-D8-Pad113)") (class "Default")
      (node (ref "U2_DISP") (pin "113") (pinfunction "D8_113") (pintype "bidirectional"))
    )
    (net (code "65") (name "unconnected-(U2_DISP-D9-Pad112)") (class "Default")
      (node (ref "U2_DISP") (pin "112") (pinfunction "D9_112") (pintype "bidirectional"))
    )
    (net (code "66") (name "unconnected-(U2_DISP-D10-Pad111)") (class "Default")
      (node (ref "U2_DISP") (pin "111") (pinfunction "D10_111") (pintype "bidirectional"))
    )
    (net (code "67") (name "unconnected-(U2_DISP-D11-Pad107)") (class "Default")
      (node (ref "U2_DISP") (pin "107") (pinfunction "D11_107") (pintype "bidirectional"))
    )
    (net (code "68") (name "unconnected-(U2_DISP-D12-Pad106)") (class "Default")
      (node (ref "U2_DISP") (pin "106") (pinfunction "D12_106") (pintype "bidirectional"))
    )
    (net (code "69") (name "unconnected-(U2_DISP-D13-Pad105)") (class "Default")
      (node (ref "U2_DISP") (pin "105") (pinfunction "D13_105") (pintype "bidirectional"))
    )
    (net (code "70") (name "unconnected-(U2_DISP-D14-Pad104)") (class "Default")
      (node (ref "U2_DISP") (pin "104") (pinfunction "D14_104") (pintype "bidirectional"))
    )
    (net (code "71") (name "unconnected-(U2_DISP-D15-Pad103)") (class "Default")
      (node (ref "U2_DISP") (pin "103") (pinfunction "D15_103") (pintype "bidirectional"))
    )
    (net (code "72") (name "unconnected-(U2_DISP-D16-Pad99)") (class "Default")
      (node (ref "U2_DISP") (pin "99") (pinfunction "D16_99") (pintype "bidirectional"))
    )
    (net (code "73") (name "unconnected-(U2_DISP-D17-Pad98)") (class "Default")
      (node (ref "U2_DISP") (pin "98") (pinfunction "D17_98") (pintype "bidirectional"))
    )
    (net (code "74") (name "unconnected-(U2_DISP-D18-Pad88)") (class "Default")
      (node (ref "U2_DISP") (pin "88") (pinfunction "D18_88") (pintype "bidirectional"))
    )
    (net (code "75") (name "unconnected-(U2_DISP-D19-Pad87)") (class "Default")
      (node (ref "U2_DISP") (pin "87") (pinfunction "D19_87") (pintype "bidirectional"))
    )
    (net (code "76") (name "unconnected-(U2_DISP-D20-Pad92)") (class "Default")
      (node (ref "U2_DISP") (pin "92") (pinfunction "D20_92") (pintype "bidirectional"))
    )
    (net (code "77") (name "unconnected-(U2_DISP-D21-Pad91)") (class "Default")
      (node (ref "U2_DISP") (pin "91") (pinfunction "D21_91") (pintype "bidirectional"))
    )
    (net (code "78") (name "unconnected-(U2_DISP-D22-Pad90)") (class "Default")
      (node (ref "U2_DISP") (pin "90") (pinfunction "D22_90") (pintype "bidirectional"))
    )
    (net (code "79") (name "unconnected-(U2_DISP-D23-Pad89)") (class "Default")
      (node (ref "U2_DISP") (pin "89") (pinfunction "D23_89") (pintype "bidirectional"))
    )
    (net (code "80") (name "unconnected-(U2_DISP-GAMAS0-Pad52)") (class "Default")
      (node (ref "U2_DISP") (pin "52") (pinfunction "GAMAS0_52") (pintype "bidirectional"))
    )
    (net (code "81") (name "unconnected-(U2_DISP-GAMAS1-Pad53)") (class "Default")
      (node (ref "U2_DISP") (pin "53") (pinfunction "GAMAS1_53") (pintype "bidirectional"))
    )
    (net (code "82") (name "unconnected-(U2_DISP-GPIO1-Pad37)") (class "Default")
      (node (ref "U2_DISP") (pin "37") (pinfunction "GPIO1_37") (pintype "bidirectional"))
    )
    (net (code "83") (name "unconnected-(U2_DISP-GPIO2-Pad38)") (class "Default")
      (node (ref "U2_DISP") (pin "38") (pinfunction "GPIO2_38") (pintype "bidirectional"))
    )
    (net (code "84") (name "unconnected-(U2_DISP-GPIO3-Pad39)") (class "Default")
      (node (ref "U2_DISP") (pin "39") (pinfunction "GPIO3_39") (pintype "bidirectional"))
    )
    (net (code "85") (name "unconnected-(U2_DISP-PWM-Pad51)") (class "Default")
      (node (ref "U2_DISP") (pin "51") (pinfunction "PWM_51") (pintype "bidirectional"))
    )
    (net (code "86") (name "unconnected-(U5_TCH-CTRL-BUSY-Pad13)") (class "Default")
      (node (ref "U5_TCH-CTRL") (pin "13") (pinfunction "BUSY_13") (pintype "bidirectional"))
    )
  )
)
